# CAN.net
KiCad netlist of a schematic drawn in Altium Designer
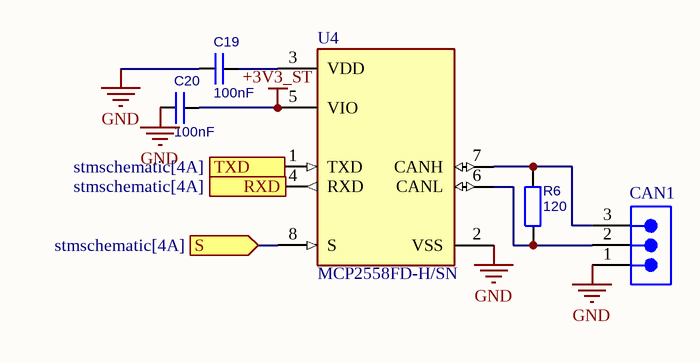
[diagram p0: CAN.SchDoc]

(export (version "E")
  (design (tool "Eeschema 10.0.6"))
  (components
    (comp (ref "C19")
      (value "100nF")
      (footprint "C0603")
      (description "Capacitor")
      (libsource (lib "General") (part "C"))
    )
    (comp (ref "C20")
      (value "100nF")
      (footprint "C0603")
      (description "Capacitor")
      (libsource (lib "General") (part "C"))
    )
    (comp (ref "CAN1")
      (value "~")
      (footprint "691321100003")
      (fields (field (name "VOLTAGE") "300V"))
      (libsource (lib "Altium Content Vault") (part "TBL - 1R - 03P - Male"))
    )
    (comp (ref "R6")
      (value "120")
      (footprint "R0603")
      (description "R")
      (libsource (lib "General") (part "R"))
    )
    (comp (ref "U4")
      (value "MCP2558FD-H/SN")
      (footprint "FP-C04-057-SN-MFG")
      (description "IC TRANSCEIVER 1/1 8SOIC")
      (fields
        (field (name "MANUFACTURER") "Microchip Technology")
        (field (name "OCTOPART") "https://octopart.com/mcp2558fd-h%2Fsn-microchip-71590966")
      )
      (libsource (lib "Altium Content Vault") (part "a9b8b5172d3d586f0ea6993265e61ec"))
    )
  )
  (nets
    (net (code "1") (name "+3V3_ST") (class "Default")
      (node (ref "C20") (pin "1") (pinfunction "1_1") (pintype "passive"))
      (node (ref "U4") (pin "5") (pinfunction "VIO_5") (pintype "power_in"))
    )
    (net (code "3") (name "/S") (class "Default")
      (node (ref "U4") (pin "8") (pinfunction "S_8") (pintype "input"))
    )
    (net (code "5") (name "GND") (class "Default")
      (node (ref "C19") (pin "2") (pinfunction "2_2") (pintype "passive"))
      (node (ref "C20") (pin "2") (pinfunction "2_2") (pintype "passive"))
      (node (ref "CAN1") (pin "1") (pinfunction "1_1") (pintype "passive"))
      (node (ref "U4") (pin "2") (pinfunction "VSS_2") (pintype "power_in"))
    )
    (net (code "6") (name "Net-(U4-CANH)") (class "Default")
      (node (ref "CAN1") (pin "3") (pinfunction "3_3") (pintype "passive"))
      (node (ref "R6") (pin "1") (pintype "passive"))
      (node (ref "U4") (pin "7") (pinfunction "CANH_7") (pintype "bidirectional"))
    )
    (net (code "7") (name "Net-(U4-CANL)") (class "Default")
      (node (ref "CAN1") (pin "2") (pinfunction "2_2") (pintype "passive"))
      (node (ref "R6") (pin "2") (pintype "passive"))
      (node (ref "U4") (pin "6") (pinfunction "CANL_6") (pintype "bidirectional"))
    )
    (net (code "8") (name "Net-(U4-VDD)") (class "Default")
      (node (ref "C19") (pin "1") (pinfunction "1_1") (pintype "passive"))
      (node (ref "U4") (pin "3") (pinfunction "VDD_3") (pintype "power_in"))
    )
    (net (code "9") (name "unconnected-(U4-RXD-Pad4)") (class "Default")
      (node (ref "U4") (pin "4") (pinfunction "RXD_4") (pintype "output"))
    )
    (net (code "10") (name "unconnected-(U4-TXD-Pad1)") (class "Default")
      (node (ref "U4") (pin "1") (pinfunction "TXD_1") (pintype "input"))
    )
  )
)
